# Placa_processamento.net
KiCad netlist of a schematic drawn in EAGLE
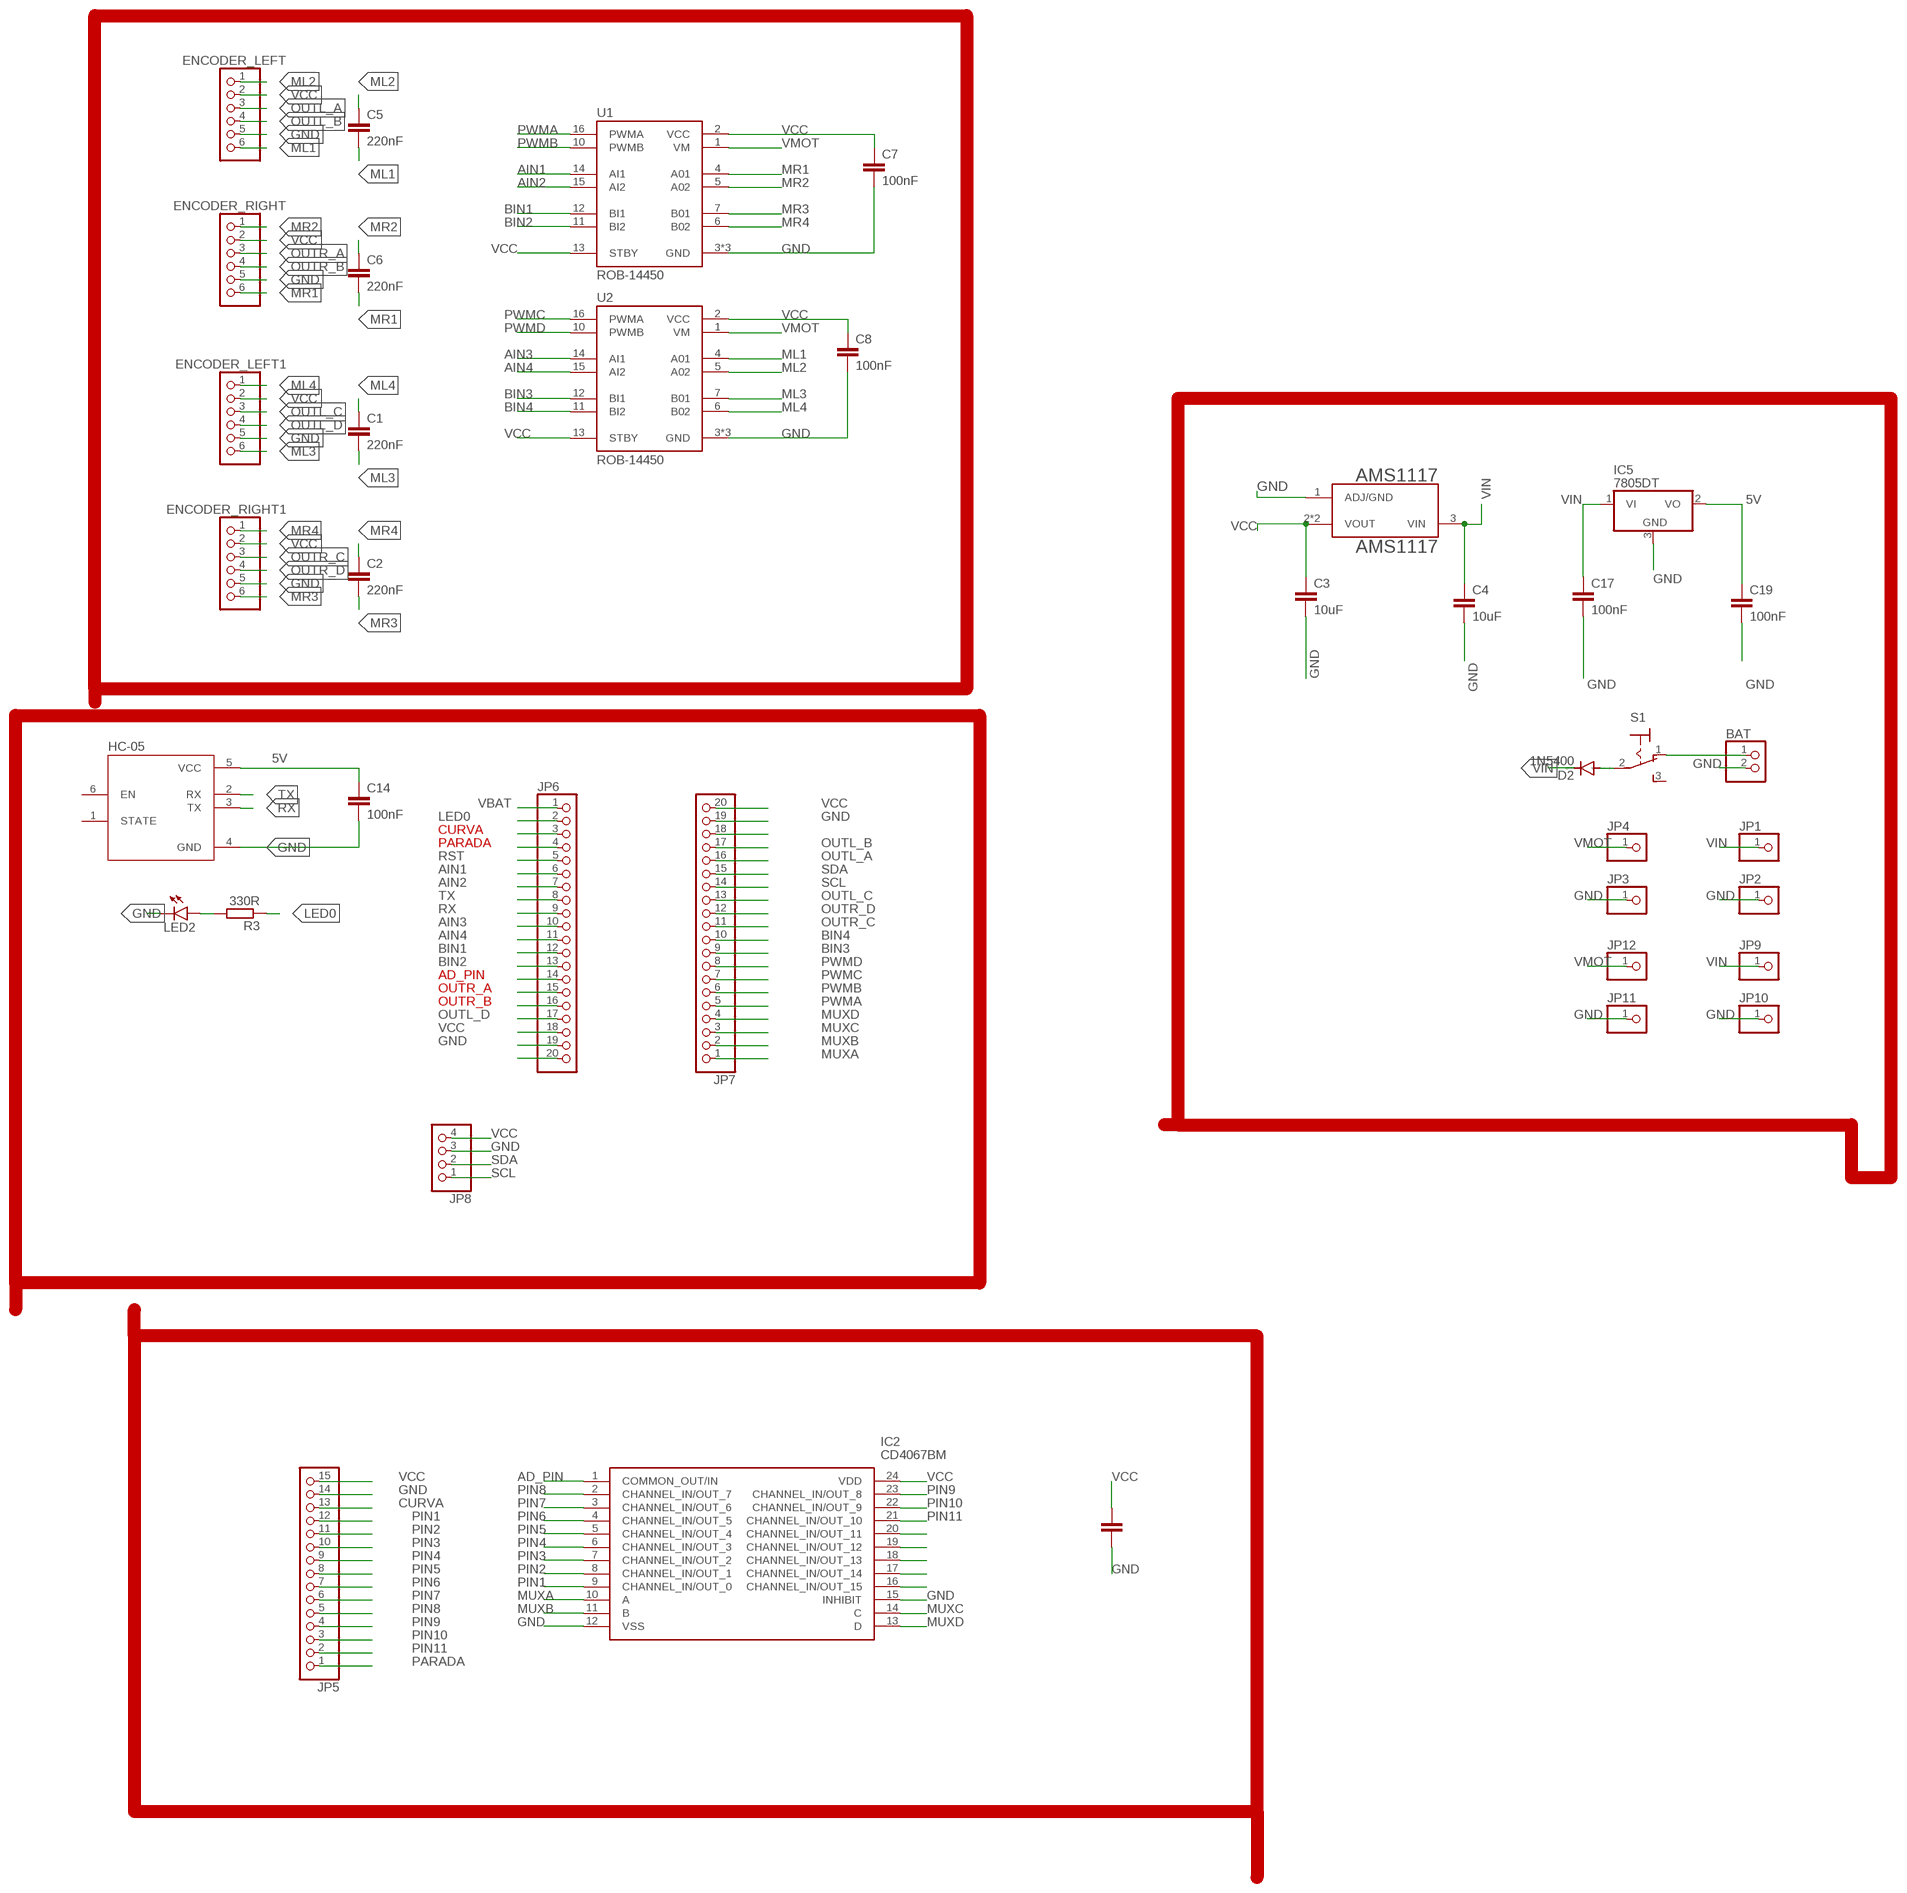
[diagram p0: schematic, sheet 1]

(export (version "E")
  (design (tool "Eeschema 10.0.6"))
  (components
    (comp (ref "AMS1117")
      (value "AMS1117")
      (footprint "eagle-import:SOT229P700X180-4N")
      (fields (field (name "MF") "Advanced Monolithic Systems"))
      (libsource (lib "eagle-import") (part "AMS1117"))
    )
    (comp (ref "BAT")
      (value "PINHD-1X2")
      (footprint "eagle-import:1X02")
      (libsource (lib "eagle-import") (part "PINHD-1X2"))
    )
    (comp (ref "C1")
      (value "220nF")
      (footprint "eagle-import:C0805")
      (libsource (lib "eagle-import") (part "C-EUC0805"))
    )
    (comp (ref "C2")
      (value "220nF")
      (footprint "eagle-import:C0805")
      (libsource (lib "eagle-import") (part "C-EUC0805"))
    )
    (comp (ref "C3")
      (value "10uF")
      (footprint "eagle-import:C0805")
      (libsource (lib "eagle-import") (part "C-EUC0805"))
    )
    (comp (ref "C4")
      (value "10uF")
      (footprint "eagle-import:C0805")
      (libsource (lib "eagle-import") (part "C-EUC0805"))
    )
    (comp (ref "C5")
      (value "220nF")
      (footprint "eagle-import:C0805")
      (libsource (lib "eagle-import") (part "C-EUC0805"))
    )
    (comp (ref "C6")
      (value "220nF")
      (footprint "eagle-import:C0805")
      (libsource (lib "eagle-import") (part "C-EUC0805"))
    )
    (comp (ref "C7")
      (value "100nF")
      (footprint "eagle-import:C0805")
      (libsource (lib "eagle-import") (part "C-EUC0805"))
    )
    (comp (ref "C8")
      (value "100nF")
      (footprint "eagle-import:C0805")
      (libsource (lib "eagle-import") (part "C-EUC0805"))
    )
    (comp (ref "C10")
      (value "100nF")
      (footprint "eagle-import:C0805")
      (libsource (lib "eagle-import") (part "C-EUC0805"))
    )
    (comp (ref "C14")
      (value "100nF")
      (footprint "eagle-import:C0805")
      (libsource (lib "eagle-import") (part "C-EUC0805"))
    )
    (comp (ref "C17")
      (value "100nF")
      (footprint "eagle-import:C0805")
      (libsource (lib "eagle-import") (part "C-EUC0805"))
    )
    (comp (ref "C19")
      (value "100nF")
      (footprint "eagle-import:C0805")
      (libsource (lib "eagle-import") (part "C-EUC0805"))
    )
    (comp (ref "D2")
      (value "1N5400")
      (footprint "eagle-import:DO201-15")
      (libsource (lib "eagle-import") (part "1N5400"))
    )
    (comp (ref "ENCODER_LEFT")
      (value "PINHD-1X6")
      (footprint "eagle-import:1X06")
      (libsource (lib "eagle-import") (part "PINHD-1X6"))
    )
    (comp (ref "ENCODER_LEFT1")
      (value "PINHD-1X6")
      (footprint "eagle-import:1X06")
      (libsource (lib "eagle-import") (part "PINHD-1X6"))
    )
    (comp (ref "ENCODER_RIGHT")
      (value "PINHD-1X6")
      (footprint "eagle-import:1X06")
      (libsource (lib "eagle-import") (part "PINHD-1X6"))
    )
    (comp (ref "ENCODER_RIGHT1")
      (value "PINHD-1X6")
      (footprint "eagle-import:1X06")
      (libsource (lib "eagle-import") (part "PINHD-1X6"))
    )
    (comp (ref "HC-05")
      (value "ZC142200")
      (footprint "eagle-import:MODULE_ZC142200")
      (fields (field (name "MF") "YKS"))
      (libsource (lib "eagle-import") (part "ZC142200"))
    )
    (comp (ref "IC2")
      (value "CD4067BM")
      (footprint "eagle-import:SOIC127P1030X265-24N")
      (fields (field (name "MOUSER_PART_NUMBER") "595-CD4067BM"))
      (libsource (lib "eagle-import") (part "CD4067BM"))
    )
    (comp (ref "IC5")
      (value "7805DT")
      (footprint "eagle-import:TO252")
      (libsource (lib "eagle-import") (part "78DT05"))
    )
    (comp (ref "JP1")
      (value "PINHD-1X1")
      (footprint "eagle-import:1X01")
      (libsource (lib "eagle-import") (part "PINHD-1X1"))
    )
    (comp (ref "JP2")
      (value "PINHD-1X1")
      (footprint "eagle-import:1X01")
      (libsource (lib "eagle-import") (part "PINHD-1X1"))
    )
    (comp (ref "JP3")
      (value "PINHD-1X1")
      (footprint "eagle-import:1X01")
      (libsource (lib "eagle-import") (part "PINHD-1X1"))
    )
    (comp (ref "JP4")
      (value "PINHD-1X1")
      (footprint "eagle-import:1X01")
      (libsource (lib "eagle-import") (part "PINHD-1X1"))
    )
    (comp (ref "JP5")
      (value "PINHD-1X15")
      (footprint "eagle-import:1X15")
      (libsource (lib "eagle-import") (part "PINHD-1X15"))
    )
    (comp (ref "JP6")
      (value "PINHD-1X20")
      (footprint "eagle-import:1X20")
      (libsource (lib "eagle-import") (part "PINHD-1X20"))
    )
    (comp (ref "JP7")
      (value "PINHD-1X20")
      (footprint "eagle-import:1X20")
      (libsource (lib "eagle-import") (part "PINHD-1X20"))
    )
    (comp (ref "JP8")
      (value "PINHD-1X4")
      (footprint "eagle-import:1X04")
      (libsource (lib "eagle-import") (part "PINHD-1X4"))
    )
    (comp (ref "JP9")
      (value "PINHD-1X1")
      (footprint "eagle-import:1X01")
      (libsource (lib "eagle-import") (part "PINHD-1X1"))
    )
    (comp (ref "JP10")
      (value "PINHD-1X1")
      (footprint "eagle-import:1X01")
      (libsource (lib "eagle-import") (part "PINHD-1X1"))
    )
    (comp (ref "JP11")
      (value "PINHD-1X1")
      (footprint "eagle-import:1X01")
      (libsource (lib "eagle-import") (part "PINHD-1X1"))
    )
    (comp (ref "JP12")
      (value "PINHD-1X1")
      (footprint "eagle-import:1X01")
      (libsource (lib "eagle-import") (part "PINHD-1X1"))
    )
    (comp (ref "LED2")
      (value "LEDCHIPLED_0805")
      (footprint "eagle-import:CHIPLED_0805")
      (libsource (lib "eagle-import") (part "LEDCHIPLED_0805"))
    )
    (comp (ref "R3")
      (value "330R")
      (footprint "eagle-import:R0805")
      (libsource (lib "eagle-import") (part "R-EU_R0805"))
    )
    (comp (ref "S1")
      (value "320-916")
      (footprint "eagle-import:320-916")
      (libsource (lib "eagle-import") (part "320-916"))
    )
    (comp (ref "U1")
      (value "ROB-14450")
      (footprint "eagle-import:MODULE_ROB-14450")
      (fields (field (name "MF") "SparkFun Electronics"))
      (libsource (lib "eagle-import") (part "ROB-14450"))
    )
    (comp (ref "U2")
      (value "ROB-14450")
      (footprint "eagle-import:MODULE_ROB-14450")
      (fields (field (name "MF") "SparkFun Electronics"))
      (libsource (lib "eagle-import") (part "ROB-14450"))
    )
  )
  (nets
    (net (code "1") (name "/5V") (class "Default")
      (node (ref "C14") (pin "1") (pinfunction "1_1") (pintype "passive"))
      (node (ref "C19") (pin "1") (pinfunction "1_1") (pintype "passive"))
      (node (ref "HC-05") (pin "5") (pinfunction "VCC_5") (pintype "power_in"))
      (node (ref "IC5") (pin "2") (pinfunction "VO_2") (pintype "passive"))
    )
    (net (code "2") (name "/AD_PIN") (class "Default")
      (node (ref "IC2") (pin "1") (pinfunction "COMMON_OUT/IN_1") (pintype "bidirectional"))
      (node (ref "JP6") (pin "14") (pinfunction "14_14") (pintype "passive"))
    )
    (net (code "3") (name "/AIN1") (class "Default")
      (node (ref "JP6") (pin "6") (pinfunction "6_6") (pintype "passive"))
      (node (ref "U1") (pin "14") (pinfunction "AI1_14") (pintype "input"))
    )
    (net (code "4") (name "/AIN2") (class "Default")
      (node (ref "JP6") (pin "7") (pinfunction "7_7") (pintype "passive"))
      (node (ref "U1") (pin "15") (pinfunction "AI2_15") (pintype "input"))
    )
    (net (code "5") (name "/AIN3") (class "Default")
      (node (ref "JP6") (pin "10") (pinfunction "10_10") (pintype "passive"))
      (node (ref "U2") (pin "14") (pinfunction "AI1_14") (pintype "input"))
    )
    (net (code "6") (name "/AIN4") (class "Default")
      (node (ref "JP6") (pin "11") (pinfunction "11_11") (pintype "passive"))
      (node (ref "U2") (pin "15") (pinfunction "AI2_15") (pintype "input"))
    )
    (net (code "7") (name "/BIN1") (class "Default")
      (node (ref "JP6") (pin "12") (pinfunction "12_12") (pintype "passive"))
      (node (ref "U1") (pin "12") (pinfunction "BI1_12") (pintype "input"))
    )
    (net (code "8") (name "/BIN2") (class "Default")
      (node (ref "JP6") (pin "13") (pinfunction "13_13") (pintype "passive"))
      (node (ref "U1") (pin "11") (pinfunction "BI2_11") (pintype "input"))
    )
    (net (code "9") (name "/BIN3") (class "Default")
      (node (ref "JP7") (pin "9") (pinfunction "9_9") (pintype "passive"))
      (node (ref "U2") (pin "12") (pinfunction "BI1_12") (pintype "input"))
    )
    (net (code "10") (name "/BIN4") (class "Default")
      (node (ref "JP7") (pin "10") (pinfunction "10_10") (pintype "passive"))
      (node (ref "U2") (pin "11") (pinfunction "BI2_11") (pintype "input"))
    )
    (net (code "11") (name "/CURVA") (class "Default")
      (node (ref "JP5") (pin "13") (pinfunction "13_13") (pintype "passive"))
      (node (ref "JP6") (pin "3") (pinfunction "3_3") (pintype "passive"))
    )
    (net (code "12") (name "/MUXA") (class "Default")
      (node (ref "IC2") (pin "10") (pinfunction "A_10") (pintype "bidirectional"))
      (node (ref "JP7") (pin "1") (pinfunction "1_1") (pintype "passive"))
    )
    (net (code "13") (name "/MUXB") (class "Default")
      (node (ref "IC2") (pin "11") (pinfunction "B_11") (pintype "bidirectional"))
      (node (ref "JP7") (pin "2") (pinfunction "2_2") (pintype "passive"))
    )
    (net (code "14") (name "/MUXC") (class "Default")
      (node (ref "IC2") (pin "14") (pinfunction "C_14") (pintype "bidirectional"))
      (node (ref "JP7") (pin "3") (pinfunction "3_3") (pintype "passive"))
    )
    (net (code "15") (name "/MUXD") (class "Default")
      (node (ref "IC2") (pin "13") (pinfunction "D_13") (pintype "bidirectional"))
      (node (ref "JP7") (pin "4") (pinfunction "4_4") (pintype "passive"))
    )
    (net (code "16") (name "/PARADA") (class "Default")
      (node (ref "JP5") (pin "1") (pinfunction "1_1") (pintype "passive"))
      (node (ref "JP6") (pin "4") (pinfunction "4_4") (pintype "passive"))
    )
    (net (code "17") (name "/PIN1") (class "Default")
      (node (ref "IC2") (pin "9") (pinfunction "CHANNEL_IN/OUT_0_9") (pintype "bidirectional"))
      (node (ref "JP5") (pin "12") (pinfunction "12_12") (pintype "passive"))
    )
    (net (code "18") (name "/PIN2") (class "Default")
      (node (ref "IC2") (pin "8") (pinfunction "CHANNEL_IN/OUT_1_8") (pintype "bidirectional"))
      (node (ref "JP5") (pin "11") (pinfunction "11_11") (pintype "passive"))
    )
    (net (code "19") (name "/PIN3") (class "Default")
      (node (ref "IC2") (pin "7") (pinfunction "CHANNEL_IN/OUT_2_7") (pintype "bidirectional"))
      (node (ref "JP5") (pin "10") (pinfunction "10_10") (pintype "passive"))
    )
    (net (code "20") (name "/PIN4") (class "Default")
      (node (ref "IC2") (pin "6") (pinfunction "CHANNEL_IN/OUT_3_6") (pintype "bidirectional"))
      (node (ref "JP5") (pin "9") (pinfunction "9_9") (pintype "passive"))
    )
    (net (code "21") (name "/PIN5") (class "Default")
      (node (ref "IC2") (pin "5") (pinfunction "CHANNEL_IN/OUT_4_5") (pintype "bidirectional"))
      (node (ref "JP5") (pin "8") (pinfunction "8_8") (pintype "passive"))
    )
    (net (code "22") (name "/PIN6") (class "Default")
      (node (ref "IC2") (pin "4") (pinfunction "CHANNEL_IN/OUT_5_4") (pintype "bidirectional"))
      (node (ref "JP5") (pin "7") (pinfunction "7_7") (pintype "passive"))
    )
    (net (code "23") (name "/PIN7") (class "Default")
      (node (ref "IC2") (pin "3") (pinfunction "CHANNEL_IN/OUT_6_3") (pintype "bidirectional"))
      (node (ref "JP5") (pin "6") (pinfunction "6_6") (pintype "passive"))
    )
    (net (code "24") (name "/PIN8") (class "Default")
      (node (ref "IC2") (pin "2") (pinfunction "CHANNEL_IN/OUT_7_2") (pintype "bidirectional"))
      (node (ref "JP5") (pin "5") (pinfunction "5_5") (pintype "passive"))
    )
    (net (code "25") (name "/PIN9") (class "Default")
      (node (ref "IC2") (pin "23") (pinfunction "CHANNEL_IN/OUT_8_23") (pintype "bidirectional"))
      (node (ref "JP5") (pin "4") (pinfunction "4_4") (pintype "passive"))
    )
    (net (code "26") (name "/PIN10") (class "Default")
      (node (ref "IC2") (pin "22") (pinfunction "CHANNEL_IN/OUT_9_22") (pintype "bidirectional"))
      (node (ref "JP5") (pin "3") (pinfunction "3_3") (pintype "passive"))
    )
    (net (code "27") (name "/PIN11") (class "Default")
      (node (ref "IC2") (pin "21") (pinfunction "CHANNEL_IN/OUT_10_21") (pintype "bidirectional"))
      (node (ref "JP5") (pin "2") (pinfunction "2_2") (pintype "passive"))
    )
    (net (code "28") (name "/PWMA") (class "Default")
      (node (ref "JP7") (pin "5") (pinfunction "5_5") (pintype "passive"))
      (node (ref "U1") (pin "16") (pinfunction "PWMA_16") (pintype "input"))
    )
    (net (code "29") (name "/PWMB") (class "Default")
      (node (ref "JP7") (pin "6") (pinfunction "6_6") (pintype "passive"))
      (node (ref "U1") (pin "10") (pinfunction "PWMB_10") (pintype "input"))
    )
    (net (code "30") (name "/PWMC") (class "Default")
      (node (ref "JP7") (pin "7") (pinfunction "7_7") (pintype "passive"))
      (node (ref "U2") (pin "16") (pinfunction "PWMA_16") (pintype "input"))
    )
    (net (code "31") (name "/PWMD") (class "Default")
      (node (ref "JP7") (pin "8") (pinfunction "8_8") (pintype "passive"))
      (node (ref "U2") (pin "10") (pinfunction "PWMB_10") (pintype "input"))
    )
    (net (code "32") (name "/RST") (class "Default")
      (node (ref "JP6") (pin "5") (pinfunction "5_5") (pintype "passive"))
    )
    (net (code "33") (name "/SCL") (class "Default")
      (node (ref "JP7") (pin "14") (pinfunction "14_14") (pintype "passive"))
      (node (ref "JP8") (pin "1") (pinfunction "1_1") (pintype "passive"))
    )
    (net (code "34") (name "/SDA") (class "Default")
      (node (ref "JP7") (pin "15") (pinfunction "15_15") (pintype "passive"))
      (node (ref "JP8") (pin "2") (pinfunction "2_2") (pintype "passive"))
    )
    (net (code "35") (name "/VBAT") (class "Default")
      (node (ref "JP6") (pin "1") (pinfunction "1_1") (pintype "passive"))
    )
    (net (code "36") (name "/VMOT") (class "Default")
      (node (ref "JP12") (pin "1") (pinfunction "1_1") (pintype "passive"))
      (node (ref "JP4") (pin "1") (pinfunction "1_1") (pintype "passive"))
      (node (ref "U1") (pin "1") (pinfunction "VM_1") (pintype "power_in"))
      (node (ref "U2") (pin "1") (pinfunction "VM_1") (pintype "power_in"))
    )
    (net (code "37") (name "GND") (class "Default")
      (node (ref "AMS1117") (pin "1") (pinfunction "ADJ/GND_1") (pintype "power_in"))
      (node (ref "BAT") (pin "2") (pinfunction "2_2") (pintype "passive"))
      (node (ref "C10") (pin "2") (pinfunction "2_2") (pintype "passive"))
      (node (ref "C14") (pin "2") (pinfunction "2_2") (pintype "passive"))
      (node (ref "C17") (pin "2") (pinfunction "2_2") (pintype "passive"))
      (node (ref "C19") (pin "2") (pinfunction "2_2") (pintype "passive"))
      (node (ref "C3") (pin "2") (pinfunction "2_2") (pintype "passive"))
      (node (ref "C4") (pin "2") (pinfunction "2_2") (pintype "passive"))
      (node (ref "C7") (pin "2") (pinfunction "2_2") (pintype "passive"))
      (node (ref "C8") (pin "2") (pinfunction "2_2") (pintype "passive"))
      (node (ref "ENCODER_LEFT") (pin "5") (pinfunction "5_5") (pintype "passive"))
      (node (ref "ENCODER_LEFT1") (pin "5") (pinfunction "5_5") (pintype "passive"))
      (node (ref "ENCODER_RIGHT") (pin "5") (pinfunction "5_5") (pintype "passive"))
      (node (ref "ENCODER_RIGHT1") (pin "5") (pinfunction "5_5") (pintype "passive"))
      (node (ref "HC-05") (pin "4") (pinfunction "GND_4") (pintype "power_in"))
      (node (ref "IC2") (pin "12") (pinfunction "VSS_12") (pintype "bidirectional"))
      (node (ref "IC2") (pin "15") (pinfunction "INHIBIT_15") (pintype "bidirectional"))
      (node (ref "IC5") (pin "3") (pinfunction "GND_3") (pintype "passive"))
      (node (ref "JP10") (pin "1") (pinfunction "1_1") (pintype "passive"))
      (node (ref "JP11") (pin "1") (pinfunction "1_1") (pintype "passive"))
      (node (ref "JP2") (pin "1") (pinfunction "1_1") (pintype "passive"))
      (node (ref "JP3") (pin "1") (pinfunction "1_1") (pintype "passive"))
      (node (ref "JP5") (pin "14") (pinfunction "14_14") (pintype "passive"))
      (node (ref "JP6") (pin "19") (pinfunction "19_19") (pintype "passive"))
      (node (ref "JP7") (pin "19") (pinfunction "19_19") (pintype "passive"))
      (node (ref "JP8") (pin "3") (pinfunction "3_3") (pintype "passive"))
      (node (ref "LED2") (pin "C") (pinfunction "C_C") (pintype "passive"))
      (node (ref "U1") (pin "3") (pinfunction "GND_3") (pintype "power_in"))
      (node (ref "U1") (pin "8") (pinfunction "GND_8") (pintype "power_in"))
      (node (ref "U1") (pin "9") (pinfunction "GND_9") (pintype "power_in"))
      (node (ref "U2") (pin "3") (pinfunction "GND_3") (pintype "power_in"))
      (node (ref "U2") (pin "8") (pinfunction "GND_8") (pintype "power_in"))
      (node (ref "U2") (pin "9") (pinfunction "GND_9") (pintype "power_in"))
    )
    (net (code "38") (name "LED0") (class "Default")
      (node (ref "JP6") (pin "2") (pinfunction "2_2") (pintype "passive"))
      (node (ref "R3") (pin "1") (pinfunction "1_1") (pintype "passive"))
    )
    (net (code "39") (name "ML1") (class "Default")
      (node (ref "C5") (pin "2") (pinfunction "2_2") (pintype "passive"))
      (node (ref "ENCODER_LEFT") (pin "6") (pinfunction "6_6") (pintype "passive"))
      (node (ref "U2") (pin "4") (pinfunction "A01_4") (pintype "output"))
    )
    (net (code "40") (name "ML2") (class "Default")
      (node (ref "C5") (pin "1") (pinfunction "1_1") (pintype "passive"))
      (node (ref "ENCODER_LEFT") (pin "1") (pinfunction "1_1") (pintype "passive"))
      (node (ref "U2") (pin "5") (pinfunction "A02_5") (pintype "output"))
    )
    (net (code "41") (name "ML3") (class "Default")
      (node (ref "C1") (pin "2") (pinfunction "2_2") (pintype "passive"))
      (node (ref "ENCODER_LEFT1") (pin "6") (pinfunction "6_6") (pintype "passive"))
      (node (ref "U2") (pin "7") (pinfunction "B01_7") (pintype "output"))
    )
    (net (code "42") (name "ML4") (class "Default")
      (node (ref "C1") (pin "1") (pinfunction "1_1") (pintype "passive"))
      (node (ref "ENCODER_LEFT1") (pin "1") (pinfunction "1_1") (pintype "passive"))
      (node (ref "U2") (pin "6") (pinfunction "B02_6") (pintype "output"))
    )
    (net (code "43") (name "MR1") (class "Default")
      (node (ref "C6") (pin "2") (pinfunction "2_2") (pintype "passive"))
      (node (ref "ENCODER_RIGHT") (pin "6") (pinfunction "6_6") (pintype "passive"))
      (node (ref "U1") (pin "4") (pinfunction "A01_4") (pintype "output"))
    )
    (net (code "44") (name "MR2") (class "Default")
      (node (ref "C6") (pin "1") (pinfunction "1_1") (pintype "passive"))
      (node (ref "ENCODER_RIGHT") (pin "1") (pinfunction "1_1") (pintype "passive"))
      (node (ref "U1") (pin "5") (pinfunction "A02_5") (pintype "output"))
    )
    (net (code "45") (name "MR3") (class "Default")
      (node (ref "C2") (pin "2") (pinfunction "2_2") (pintype "passive"))
      (node (ref "ENCODER_RIGHT1") (pin "6") (pinfunction "6_6") (pintype "passive"))
      (node (ref "U1") (pin "7") (pinfunction "B01_7") (pintype "output"))
    )
    (net (code "46") (name "MR4") (class "Default")
      (node (ref "C2") (pin "1") (pinfunction "1_1") (pintype "passive"))
      (node (ref "ENCODER_RIGHT1") (pin "1") (pinfunction "1_1") (pintype "passive"))
      (node (ref "U1") (pin "6") (pinfunction "B02_6") (pintype "output"))
    )
    (net (code "47") (name "Net-(LED2-PadA)") (class "Default")
      (node (ref "LED2") (pin "A") (pinfunction "A_A") (pintype "passive"))
      (node (ref "R3") (pin "2") (pinfunction "2_2") (pintype "passive"))
    )
    (net (code "48") (name "Net-(S1-O)") (class "Default")
      (node (ref "BAT") (pin "1") (pinfunction "1_1") (pintype "passive"))
      (node (ref "S1") (pin "1") (pinfunction "O_1") (pintype "passive"))
    )
    (net (code "49") (name "Net-(S1-P)") (class "Default")
      (node (ref "D2") (pin "A") (pinfunction "A_A") (pintype "passive"))
      (node (ref "S1") (pin "2") (pinfunction "P_2") (pintype "passive"))
    )
    (net (code "50") (name "OUTL_A") (class "Default")
      (node (ref "ENCODER_LEFT") (pin "3") (pinfunction "3_3") (pintype "passive"))
      (node (ref "JP7") (pin "16") (pinfunction "16_16") (pintype "passive"))
    )
    (net (code "51") (name "OUTL_B") (class "Default")
      (node (ref "ENCODER_LEFT") (pin "4") (pinfunction "4_4") (pintype "passive"))
      (node (ref "JP7") (pin "17") (pinfunction "17_17") (pintype "passive"))
    )
    (net (code "52") (name "OUTL_C") (class "Default")
      (node (ref "ENCODER_LEFT1") (pin "3") (pinfunction "3_3") (pintype "passive"))
      (node (ref "JP7") (pin "13") (pinfunction "13_13") (pintype "passive"))
    )
    (net (code "53") (name "OUTL_D") (class "Default")
      (node (ref "ENCODER_LEFT1") (pin "4") (pinfunction "4_4") (pintype "passive"))
      (node (ref "JP6") (pin "17") (pinfunction "17_17") (pintype "passive"))
    )
    (net (code "54") (name "OUTR_A") (class "Default")
      (node (ref "ENCODER_RIGHT") (pin "3") (pinfunction "3_3") (pintype "passive"))
      (node (ref "JP6") (pin "15") (pinfunction "15_15") (pintype "passive"))
    )
    (net (code "55") (name "OUTR_B") (class "Default")
      (node (ref "ENCODER_RIGHT") (pin "4") (pinfunction "4_4") (pintype "passive"))
      (node (ref "JP6") (pin "16") (pinfunction "16_16") (pintype "passive"))
    )
    (net (code "56") (name "OUTR_C") (class "Default")
      (node (ref "ENCODER_RIGHT1") (pin "3") (pinfunction "3_3") (pintype "passive"))
      (node (ref "JP7") (pin "11") (pinfunction "11_11") (pintype "passive"))
    )
    (net (code "57") (name "OUTR_D") (class "Default")
      (node (ref "ENCODER_RIGHT1") (pin "4") (pinfunction "4_4") (pintype "passive"))
      (node (ref "JP7") (pin "12") (pinfunction "12_12") (pintype "passive"))
    )
    (net (code "58") (name "RX") (class "Default")
      (node (ref "HC-05") (pin "3") (pinfunction "TX_3") (pintype "output"))
      (node (ref "JP6") (pin "9") (pinfunction "9_9") (pintype "passive"))
    )
    (net (code "59") (name "TX") (class "Default")
      (node (ref "HC-05") (pin "2") (pinfunction "RX_2") (pintype "input"))
      (node (ref "JP6") (pin "8") (pinfunction "8_8") (pintype "passive"))
    )
    (net (code "60") (name "VCC") (class "Default")
      (node (ref "AMS1117") (pin "2") (pinfunction "VOUT_2") (pintype "output"))
      (node (ref "AMS1117") (pin "4") (pinfunction "VOUT_4") (pintype "output"))
      (node (ref "C10") (pin "1") (pinfunction "1_1") (pintype "passive"))
      (node (ref "C3") (pin "1") (pinfunction "1_1") (pintype "passive"))
      (node (ref "C7") (pin "1") (pinfunction "1_1") (pintype "passive"))
      (node (ref "C8") (pin "1") (pinfunction "1_1") (pintype "passive"))
      (node (ref "ENCODER_LEFT") (pin "2") (pinfunction "2_2") (pintype "passive"))
      (node (ref "ENCODER_LEFT1") (pin "2") (pinfunction "2_2") (pintype "passive"))
      (node (ref "ENCODER_RIGHT") (pin "2") (pinfunction "2_2") (pintype "passive"))
      (node (ref "ENCODER_RIGHT1") (pin "2") (pinfunction "2_2") (pintype "passive"))
      (node (ref "IC2") (pin "24") (pinfunction "VDD_24") (pintype "bidirectional"))
      (node (ref "JP5") (pin "15") (pinfunction "15_15") (pintype "passive"))
      (node (ref "JP6") (pin "18") (pinfunction "18_18") (pintype "passive"))
      (node (ref "JP7") (pin "20") (pinfunction "20_20") (pintype "passive"))
      (node (ref "JP8") (pin "4") (pinfunction "4_4") (pintype "passive"))
      (node (ref "U1") (pin "13") (pinfunction "STBY_13") (pintype "input"))
      (node (ref "U1") (pin "2") (pinfunction "VCC_2") (pintype "power_in"))
      (node (ref "U2") (pin "13") (pinfunction "STBY_13") (pintype "input"))
      (node (ref "U2") (pin "2") (pinfunction "VCC_2") (pintype "power_in"))
    )
    (net (code "61") (name "VIN") (class "Default")
      (node (ref "AMS1117") (pin "3") (pinfunction "VIN_3") (pintype "input"))
      (node (ref "C17") (pin "1") (pinfunction "1_1") (pintype "passive"))
      (node (ref "C4") (pin "1") (pinfunction "1_1") (pintype "passive"))
      (node (ref "D2") (pin "C") (pinfunction "C_C") (pintype "passive"))
      (node (ref "IC5") (pin "1") (pinfunction "VI_1") (pintype "input"))
      (node (ref "JP1") (pin "1") (pinfunction "1_1") (pintype "passive"))
      (node (ref "JP9") (pin "1") (pinfunction "1_1") (pintype "passive"))
    )
    (net (code "62") (name "unconnected-(HC-05-EN-Pad6)") (class "Default")
      (node (ref "HC-05") (pin "6") (pinfunction "EN_6") (pintype "input"))
    )
    (net (code "63") (name "unconnected-(HC-05-STATE-Pad1)") (class "Default")
      (node (ref "HC-05") (pin "1") (pinfunction "STATE_1") (pintype "input"))
    )
    (net (code "64") (name "unconnected-(IC2-CHANNEL_IN{slash}OUT_11-Pad20)") (class "Default")
      (node (ref "IC2") (pin "20") (pinfunction "CHANNEL_IN/OUT_11_20") (pintype "bidirectional"))
    )
    (net (code "65") (name "unconnected-(IC2-CHANNEL_IN{slash}OUT_12-Pad19)") (class "Default")
      (node (ref "IC2") (pin "19") (pinfunction "CHANNEL_IN/OUT_12_19") (pintype "bidirectional"))
    )
    (net (code "66") (name "unconnected-(IC2-CHANNEL_IN{slash}OUT_13-Pad18)") (class "Default")
      (node (ref "IC2") (pin "18") (pinfunction "CHANNEL_IN/OUT_13_18") (pintype "bidirectional"))
    )
    (net (code "67") (name "unconnected-(IC2-CHANNEL_IN{slash}OUT_14-Pad17)") (class "Default")
      (node (ref "IC2") (pin "17") (pinfunction "CHANNEL_IN/OUT_14_17") (pintype "bidirectional"))
    )
    (net (code "68") (name "unconnected-(IC2-CHANNEL_IN{slash}OUT_15-Pad16)") (class "Default")
      (node (ref "IC2") (pin "16") (pinfunction "CHANNEL_IN/OUT_15_16") (pintype "bidirectional"))
    )
    (net (code "69") (name "unconnected-(JP6-Pad20)") (class "Default")
      (node (ref "JP6") (pin "20") (pinfunction "20_20") (pintype "passive"))
    )
    (net (code "70") (name "unconnected-(JP7-Pad18)") (class "Default")
      (node (ref "JP7") (pin "18") (pinfunction "18_18") (pintype "passive"))
    )
    (net (code "71") (name "unconnected-(S1-S-Pad3)") (class "Default")
      (node (ref "S1") (pin "3") (pinfunction "S_3") (pintype "passive"))
    )
  )
)
